# 12V_LS.net
KiCad netlist of a schematic drawn in Altium Designer
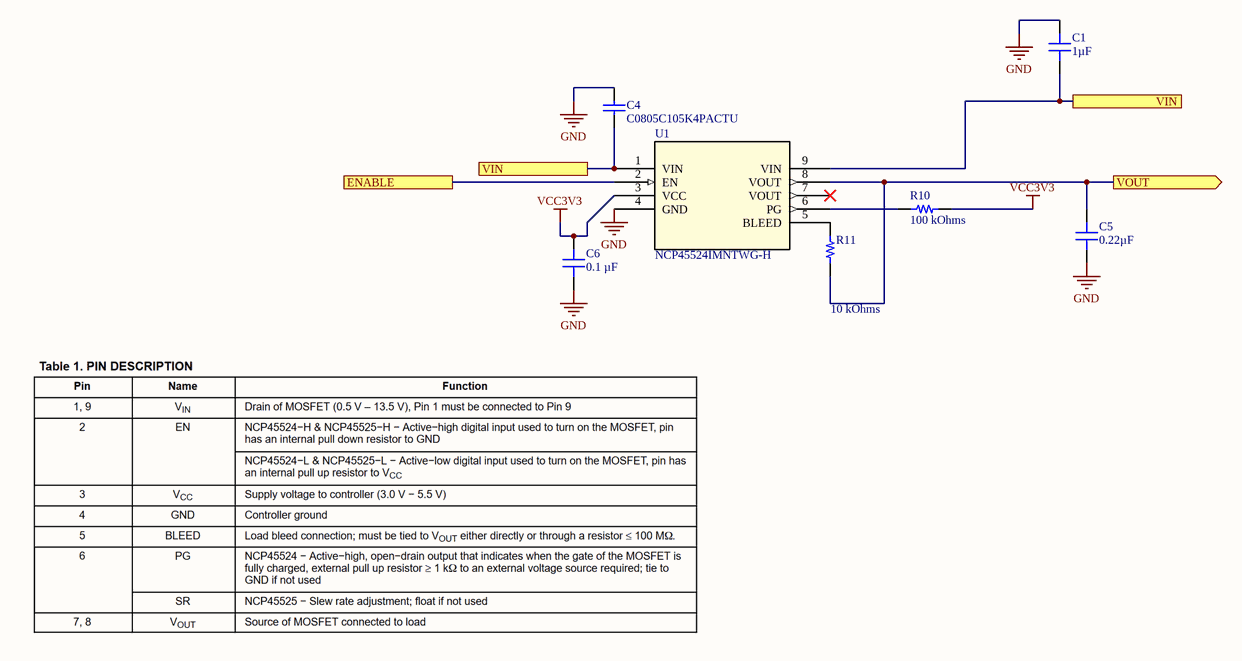
[diagram p0: 12V_LS.SchDoc]

(export (version "E")
  (design (tool "Eeschema 10.0.6"))
  (components
    (comp (ref "C1")
      (value "1µF")
      (footprint "CAP 0805_2012")
      (description "CAP CER 1UF 6.3V X5R 0805")
      (fields (field (name "PART NUMBER") "LGC26D105MAT2S1") (field (name "MANUFACTURER") "AVX Corporation"))
      (libsource (lib "Celestial Altium Library - altium_library") (part "Capacitor"))
    )
    (comp (ref "C4")
      (value "C0805C105K4PACTU")
      (footprint "CAPC2013X145X50LL20T25")
      (fields (field (name "MANUFACTURER") "Kemet"))
      (libsource (lib "Altium Content Vault") (part "CAP"))
    )
    (comp (ref "C5")
      (value "0.22µF")
      (footprint "CAP 0805_2012")
      (description "CAP CER 0.22UF 50V X7R 0805")
      (fields (field (name "PART NUMBER") "MM055C224KCZ2A") (field (name "MANUFACTURER") "AVX Corporation"))
      (libsource (lib "Celestial Altium Library - altium_library") (part "Capacitor"))
    )
    (comp (ref "C6")
      (value "0.1 µF")
      (footprint "CAP 0805_2012")
      (description "CAP CER 0.1UF 50V X7R 0805")
      (fields (field (name "PART NUMBER") "CC0805MRX7R9BB104") (field (name "MANUFACTURER") "Yageo"))
      (libsource (lib "Celestial Altium Library - altium_library") (part "Capacitor"))
    )
    (comp (ref "R10")
      (value "100 kOhms")
      (footprint "RES 0603_1608")
      (description "RES 100K OHM 0.1% 1/16W 0603")
      (fields
        (field (name "PART NUMBER") "RNCS0603BKE100K")
        (field (name "MANUFACTURER") "Stackpole Electronics Inc")
      )
      (libsource (lib "Celestial Altium Library - altium_library") (part "Resistor"))
    )
    (comp (ref "R11")
      (value "10 kOhms")
      (footprint "RES 0603_1608")
      (description "RES 10K OHM 0.1% 1/16W 0603")
      (fields
        (field (name "PART NUMBER") "RNCS0603BKE10K0")
        (field (name "MANUFACTURER") "Stackpole Electronics Inc")
      )
      (libsource (lib "Celestial Altium Library - altium_library") (part "Resistor"))
    )
    (comp (ref "U1")
      (value "NCP45524IMNTWG-H")
      (footprint "SON50P200X200X100-9N:SON50P200X200X100-9N")
      (description "No Description Available")
      (fields (field (name "COPYRIGHT") "Copyright (C) 2023 Ultra Librarian. All rights reserved."))
      (libsource (lib "NCP45524IMNTWG-H") (part "NCP45524IMNTWG-H"))
    )
  )
  (nets
    (net (code "1") (name "/ENABLE") (class "Default")
      (node (ref "U1") (pin "2") (pinfunction "EN_2") (pintype "input"))
    )
    (net (code "2") (name "/VIN") (class "Default")
      (node (ref "C1") (pin "1") (pinfunction "1_1") (pintype "passive"))
      (node (ref "C4") (pin "1") (pinfunction "1_1") (pintype "passive"))
      (node (ref "U1") (pin "1") (pinfunction "VIN_1") (pintype "power_in"))
      (node (ref "U1") (pin "9") (pinfunction "VIN_9") (pintype "power_in"))
    )
    (net (code "3") (name "/VOUT") (class "Default")
      (node (ref "C5") (pin "2") (pinfunction "2_2") (pintype "passive"))
      (node (ref "R11") (pin "1") (pinfunction "1_1") (pintype "passive"))
      (node (ref "U1") (pin "8") (pinfunction "VOUT_8") (pintype "output"))
    )
    (net (code "4") (name "GND") (class "Default")
      (node (ref "C1") (pin "2") (pinfunction "2_2") (pintype "passive"))
      (node (ref "C4") (pin "2") (pinfunction "2_2") (pintype "passive"))
      (node (ref "C5") (pin "1") (pinfunction "1_1") (pintype "passive"))
      (node (ref "C6") (pin "1") (pinfunction "1_1") (pintype "passive"))
      (node (ref "U1") (pin "4") (pinfunction "GND_4") (pintype "power_in"))
    )
    (net (code "5") (name "Net-(U1-BLEED)") (class "Default")
      (node (ref "R11") (pin "2") (pinfunction "2_2") (pintype "passive"))
      (node (ref "U1") (pin "5") (pinfunction "BLEED_5") (pintype "passive"))
    )
    (net (code "6") (name "Net-(U1-PG)") (class "Default")
      (node (ref "R10") (pin "1") (pinfunction "1_1") (pintype "passive"))
      (node (ref "U1") (pin "6") (pinfunction "PG_6") (pintype "output"))
    )
    (net (code "7") (name "VCC3V3") (class "Default")
      (node (ref "C6") (pin "2") (pinfunction "2_2") (pintype "passive"))
      (node (ref "R10") (pin "2") (pinfunction "2_2") (pintype "passive"))
      (node (ref "U1") (pin "3") (pinfunction "VCC_3") (pintype "power_in"))
    )
    (net (code "8") (name "unconnected-(U1-VOUT-Pad7)") (class "Default")
      (node (ref "U1") (pin "7") (pinfunction "VOUT_7") (pintype "output+no_connect"))
    )
  )
)
